# ProPrj_C64_Printer_Interface_2025-08-30.net
KiCad netlist of a schematic drawn in EasyEDA Pro
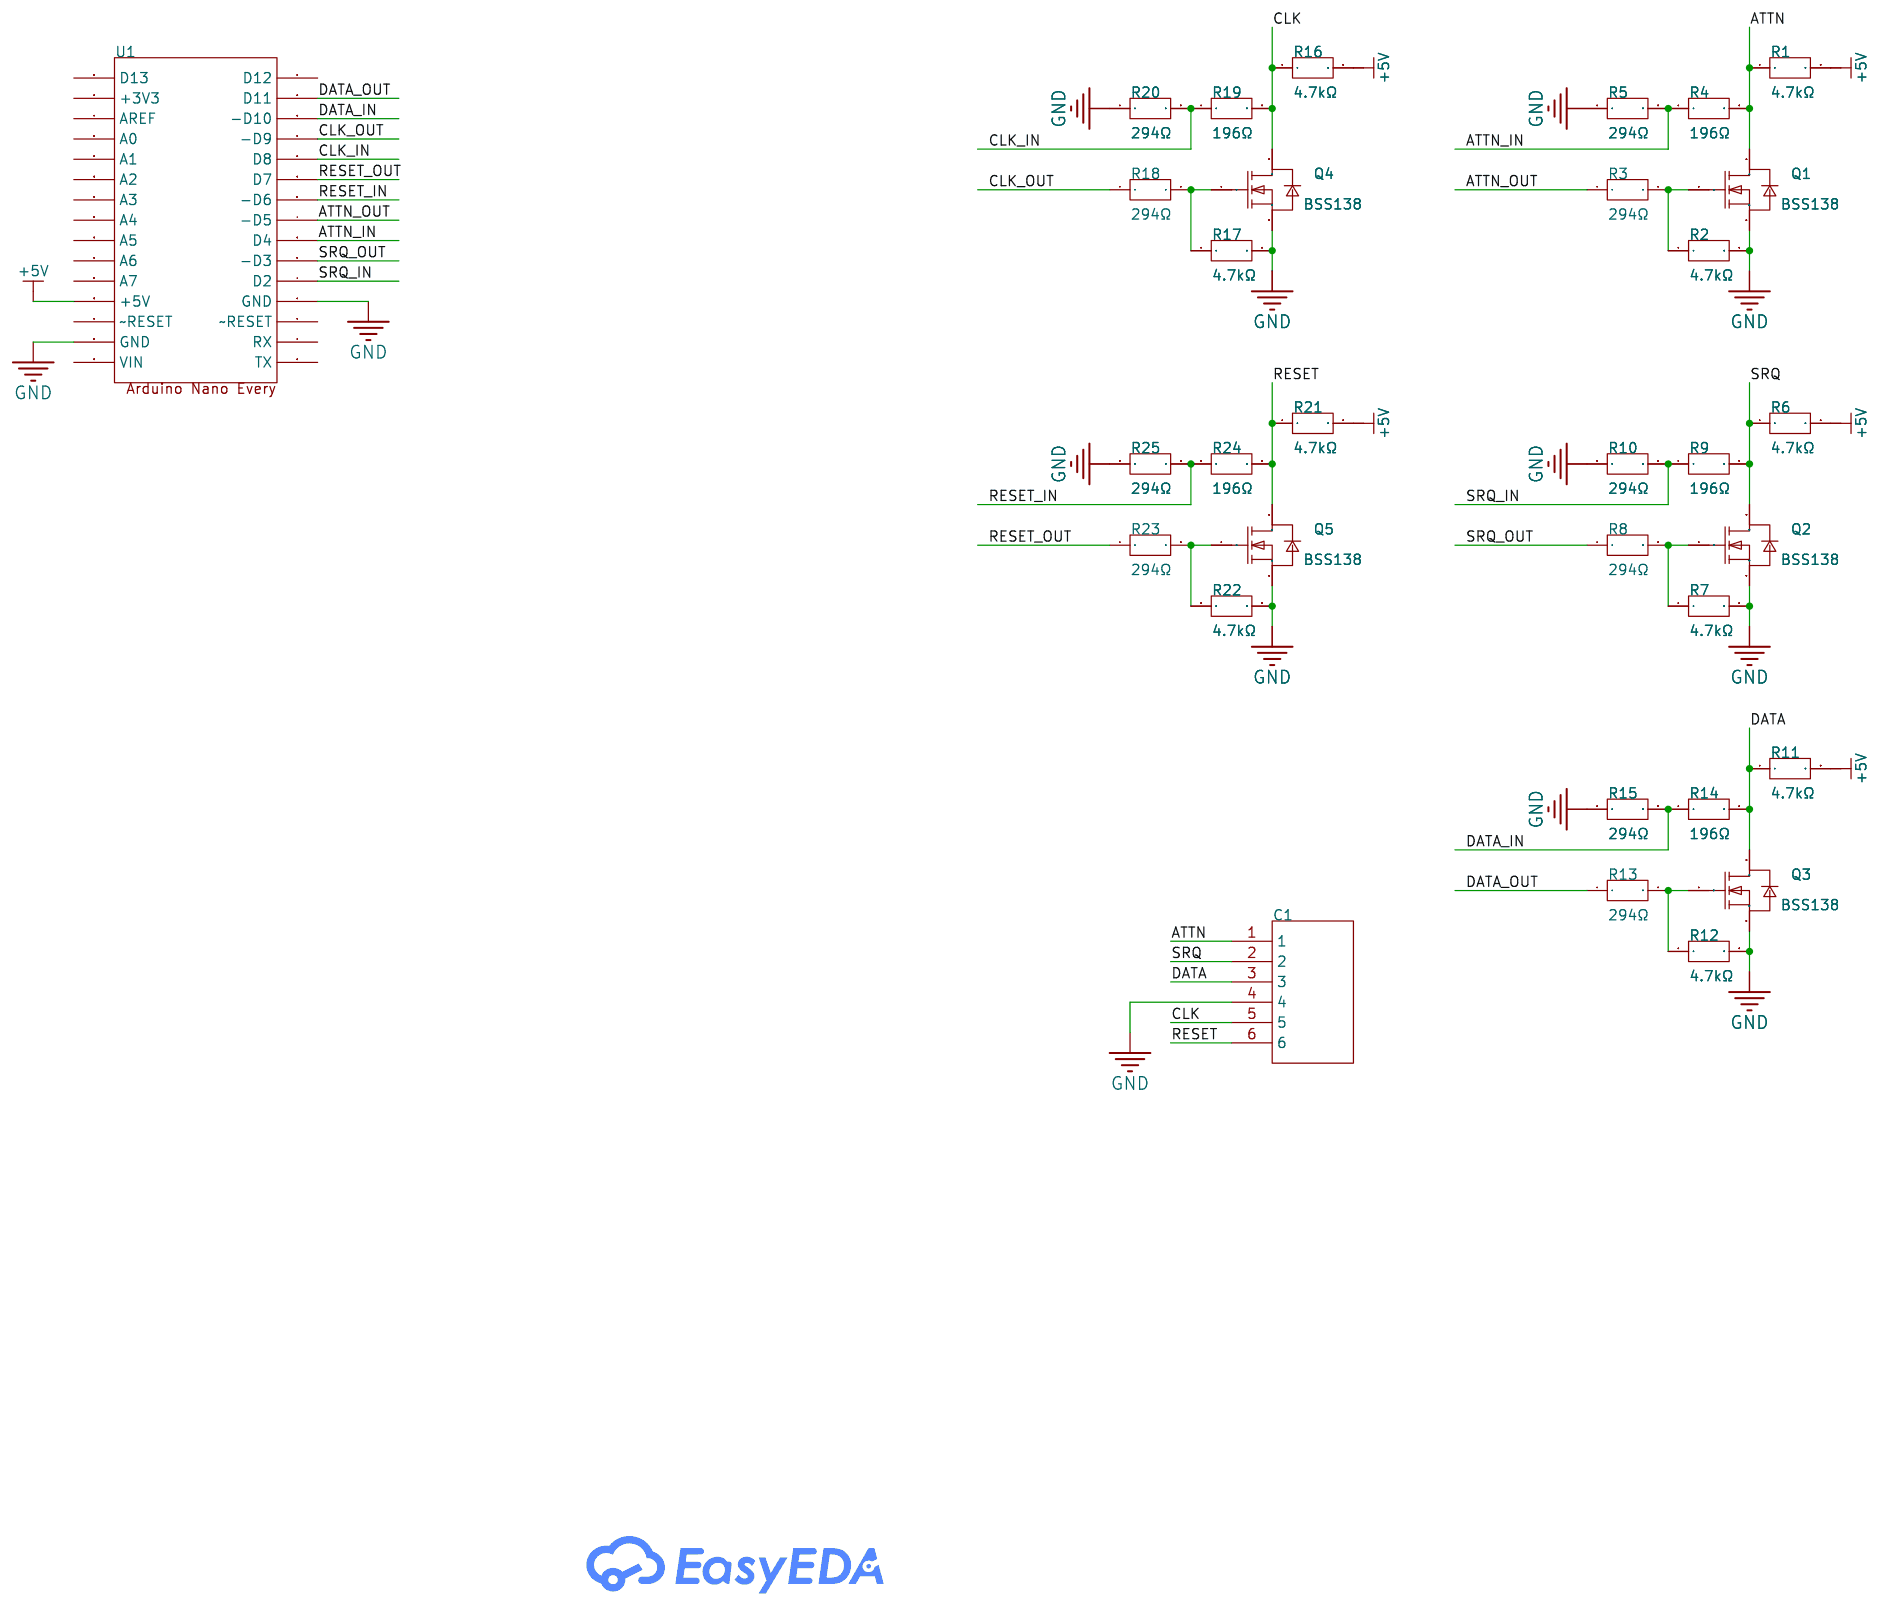
[diagram p0: schematic sheet]

(export (version "E")
  (design (tool "Eeschema 10.0.6"))
  (components
    (comp (ref "C1")
      (value "DIN 6")
      (footprint "easyedapro:FC680806")
      (libsource (lib "easyedapro") (part "FC680806 DIN 6 240°"))
    )
    (comp (ref "Q1")
      (value "BSS138")
      (footprint "easyedapro:SOT-23-3_L2.9-W1.3-P1.90-LS2.4-BR-1")
      (fields (field (name "Manufacturer") "KUU"))
      (libsource (lib "easyedapro") (part "BSS138_C3015220"))
    )
    (comp (ref "Q2")
      (value "BSS138")
      (footprint "easyedapro:SOT-23-3_L2.9-W1.3-P1.90-LS2.4-BR-1")
      (fields (field (name "Manufacturer") "KUU"))
      (libsource (lib "easyedapro") (part "BSS138_C3015220"))
    )
    (comp (ref "Q3")
      (value "BSS138")
      (footprint "easyedapro:SOT-23-3_L2.9-W1.3-P1.90-LS2.4-BR-1")
      (fields (field (name "Manufacturer") "KUU"))
      (libsource (lib "easyedapro") (part "BSS138_C3015220"))
    )
    (comp (ref "Q4")
      (value "BSS138")
      (footprint "easyedapro:SOT-23-3_L2.9-W1.3-P1.90-LS2.4-BR-1")
      (fields (field (name "Manufacturer") "KUU"))
      (libsource (lib "easyedapro") (part "BSS138_C3015220"))
    )
    (comp (ref "Q5")
      (value "BSS138")
      (footprint "easyedapro:SOT-23-3_L2.9-W1.3-P1.90-LS2.4-BR-1")
      (fields (field (name "Manufacturer") "KUU"))
      (libsource (lib "easyedapro") (part "BSS138_C3015220"))
    )
    (comp (ref "R1")
      (value "4.7kΩ")
      (footprint "easyedapro:R0805")
      (fields (field (name "Manufacturer Part") "RT0805BRD07330KL") (field (name "Manufacturer") "YAGEO(国巨)"))
      (libsource (lib "easyedapro") (part "RT0805BRD07330KL"))
    )
    (comp (ref "R2")
      (value "4.7kΩ")
      (footprint "easyedapro:R0805")
      (fields (field (name "Manufacturer Part") "RT0805BRD07330KL") (field (name "Manufacturer") "YAGEO(国巨)"))
      (libsource (lib "easyedapro") (part "RT0805BRD07330KL"))
    )
    (comp (ref "R3")
      (value "294Ω")
      (footprint "easyedapro:R0805")
      (fields (field (name "Manufacturer Part") "RT0805BRD07330KL") (field (name "Manufacturer") "YAGEO(国巨)"))
      (libsource (lib "easyedapro") (part "RT0805BRD07330KL"))
    )
    (comp (ref "R4")
      (value "196Ω")
      (footprint "easyedapro:R0805")
      (fields (field (name "Manufacturer Part") "RT0805BRD07330KL") (field (name "Manufacturer") "YAGEO(国巨)"))
      (libsource (lib "easyedapro") (part "RT0805BRD07330KL"))
    )
    (comp (ref "R5")
      (value "294Ω")
      (footprint "easyedapro:R0805")
      (fields (field (name "Manufacturer Part") "RT0805BRD07330KL") (field (name "Manufacturer") "YAGEO(国巨)"))
      (libsource (lib "easyedapro") (part "RT0805BRD07330KL"))
    )
    (comp (ref "R6")
      (value "4.7kΩ")
      (footprint "easyedapro:R0805")
      (fields (field (name "Manufacturer Part") "RT0805BRD07330KL") (field (name "Manufacturer") "YAGEO(国巨)"))
      (libsource (lib "easyedapro") (part "RT0805BRD07330KL"))
    )
    (comp (ref "R7")
      (value "4.7kΩ")
      (footprint "easyedapro:R0805")
      (fields (field (name "Manufacturer Part") "RT0805BRD07330KL") (field (name "Manufacturer") "YAGEO(国巨)"))
      (libsource (lib "easyedapro") (part "RT0805BRD07330KL"))
    )
    (comp (ref "R8")
      (value "294Ω")
      (footprint "easyedapro:R0805")
      (fields (field (name "Manufacturer Part") "RT0805BRD07330KL") (field (name "Manufacturer") "YAGEO(国巨)"))
      (libsource (lib "easyedapro") (part "RT0805BRD07330KL"))
    )
    (comp (ref "R9")
      (value "196Ω")
      (footprint "easyedapro:R0805")
      (fields (field (name "Manufacturer Part") "RT0805BRD07330KL") (field (name "Manufacturer") "YAGEO(国巨)"))
      (libsource (lib "easyedapro") (part "RT0805BRD07330KL"))
    )
    (comp (ref "R10")
      (value "294Ω")
      (footprint "easyedapro:R0805")
      (fields (field (name "Manufacturer Part") "RT0805BRD07330KL") (field (name "Manufacturer") "YAGEO(国巨)"))
      (libsource (lib "easyedapro") (part "RT0805BRD07330KL"))
    )
    (comp (ref "R11")
      (value "4.7kΩ")
      (footprint "easyedapro:R0805")
      (fields (field (name "Manufacturer Part") "RT0805BRD07330KL") (field (name "Manufacturer") "YAGEO(国巨)"))
      (libsource (lib "easyedapro") (part "RT0805BRD07330KL"))
    )
    (comp (ref "R12")
      (value "4.7kΩ")
      (footprint "easyedapro:R0805")
      (fields (field (name "Manufacturer Part") "RT0805BRD07330KL") (field (name "Manufacturer") "YAGEO(国巨)"))
      (libsource (lib "easyedapro") (part "RT0805BRD07330KL"))
    )
    (comp (ref "R13")
      (value "294Ω")
      (footprint "easyedapro:R0805")
      (fields (field (name "Manufacturer Part") "RT0805BRD07330KL") (field (name "Manufacturer") "YAGEO(国巨)"))
      (libsource (lib "easyedapro") (part "RT0805BRD07330KL"))
    )
    (comp (ref "R14")
      (value "196Ω")
      (footprint "easyedapro:R0805")
      (fields (field (name "Manufacturer Part") "RT0805BRD07330KL") (field (name "Manufacturer") "YAGEO(国巨)"))
      (libsource (lib "easyedapro") (part "RT0805BRD07330KL"))
    )
    (comp (ref "R15")
      (value "294Ω")
      (footprint "easyedapro:R0805")
      (fields (field (name "Manufacturer Part") "RT0805BRD07330KL") (field (name "Manufacturer") "YAGEO(国巨)"))
      (libsource (lib "easyedapro") (part "RT0805BRD07330KL"))
    )
    (comp (ref "R16")
      (value "4.7kΩ")
      (footprint "easyedapro:R0805")
      (fields (field (name "Manufacturer Part") "RT0805BRD07330KL") (field (name "Manufacturer") "YAGEO(国巨)"))
      (libsource (lib "easyedapro") (part "RT0805BRD07330KL"))
    )
    (comp (ref "R17")
      (value "4.7kΩ")
      (footprint "easyedapro:R0805")
      (fields (field (name "Manufacturer Part") "RT0805BRD07330KL") (field (name "Manufacturer") "YAGEO(国巨)"))
      (libsource (lib "easyedapro") (part "RT0805BRD07330KL"))
    )
    (comp (ref "R18")
      (value "294Ω")
      (footprint "easyedapro:R0805")
      (fields (field (name "Manufacturer Part") "RT0805BRD07330KL") (field (name "Manufacturer") "YAGEO(国巨)"))
      (libsource (lib "easyedapro") (part "RT0805BRD07330KL"))
    )
    (comp (ref "R19")
      (value "196Ω")
      (footprint "easyedapro:R0805")
      (fields (field (name "Manufacturer Part") "RT0805BRD07330KL") (field (name "Manufacturer") "YAGEO(国巨)"))
      (libsource (lib "easyedapro") (part "RT0805BRD07330KL"))
    )
    (comp (ref "R20")
      (value "294Ω")
      (footprint "easyedapro:R0805")
      (fields (field (name "Manufacturer Part") "RT0805BRD07330KL") (field (name "Manufacturer") "YAGEO(国巨)"))
      (libsource (lib "easyedapro") (part "RT0805BRD07330KL"))
    )
    (comp (ref "R21")
      (value "4.7kΩ")
      (footprint "easyedapro:R0805")
      (fields (field (name "Manufacturer Part") "RT0805BRD07330KL") (field (name "Manufacturer") "YAGEO(国巨)"))
      (libsource (lib "easyedapro") (part "RT0805BRD07330KL"))
    )
    (comp (ref "R22")
      (value "4.7kΩ")
      (footprint "easyedapro:R0805")
      (fields (field (name "Manufacturer Part") "RT0805BRD07330KL") (field (name "Manufacturer") "YAGEO(国巨)"))
      (libsource (lib "easyedapro") (part "RT0805BRD07330KL"))
    )
    (comp (ref "R23")
      (value "294Ω")
      (footprint "easyedapro:R0805")
      (fields (field (name "Manufacturer Part") "RT0805BRD07330KL") (field (name "Manufacturer") "YAGEO(国巨)"))
      (libsource (lib "easyedapro") (part "RT0805BRD07330KL"))
    )
    (comp (ref "R24")
      (value "196Ω")
      (footprint "easyedapro:R0805")
      (fields (field (name "Manufacturer Part") "RT0805BRD07330KL") (field (name "Manufacturer") "YAGEO(国巨)"))
      (libsource (lib "easyedapro") (part "RT0805BRD07330KL"))
    )
    (comp (ref "R25")
      (value "294Ω")
      (footprint "easyedapro:R0805")
      (fields (field (name "Manufacturer Part") "RT0805BRD07330KL") (field (name "Manufacturer") "YAGEO(国巨)"))
      (libsource (lib "easyedapro") (part "RT0805BRD07330KL"))
    )
    (comp (ref "U1")
      (value "~")
      (footprint "easyedapro:Arduino Nano Every (SMD)")
      (libsource (lib "easyedapro") (part "Arduino Nano Every"))
    )
  )
  (nets
    (net (code "1") (name "+5V") (class "Default")
      (node (ref "R1") (pin "2") (pinfunction "2_2") (pintype "unspecified"))
      (node (ref "R11") (pin "2") (pinfunction "2_2") (pintype "unspecified"))
      (node (ref "R16") (pin "2") (pinfunction "2_2") (pintype "unspecified"))
      (node (ref "R21") (pin "2") (pinfunction "2_2") (pintype "unspecified"))
      (node (ref "R6") (pin "2") (pinfunction "2_2") (pintype "unspecified"))
      (node (ref "U1") (pin "26") (pinfunction "+5V_26") (pintype "input"))
    )
    (net (code "2") (name "/ATTN") (class "Default")
      (node (ref "C1") (pin "1") (pinfunction "1_1") (pintype "input"))
      (node (ref "Q1") (pin "3") (pinfunction "D_3") (pintype "unspecified"))
      (node (ref "R1") (pin "1") (pinfunction "1_1") (pintype "unspecified"))
      (node (ref "R4") (pin "2") (pinfunction "2_2") (pintype "unspecified"))
    )
    (net (code "3") (name "/ATTN_IN") (class "Default")
      (node (ref "R4") (pin "1") (pinfunction "1_1") (pintype "unspecified"))
      (node (ref "R5") (pin "2") (pinfunction "2_2") (pintype "unspecified"))
      (node (ref "U1") (pin "6") (pinfunction "D4_6") (pintype "input"))
    )
    (net (code "4") (name "/ATTN_OUT") (class "Default")
      (node (ref "R3") (pin "1") (pinfunction "1_1") (pintype "unspecified"))
      (node (ref "U1") (pin "7") (pinfunction "-D5_7") (pintype "input"))
    )
    (net (code "5") (name "/CLK") (class "Default")
      (node (ref "C1") (pin "5") (pinfunction "5_5") (pintype "input"))
      (node (ref "Q4") (pin "3") (pinfunction "D_3") (pintype "unspecified"))
      (node (ref "R16") (pin "1") (pinfunction "1_1") (pintype "unspecified"))
      (node (ref "R19") (pin "2") (pinfunction "2_2") (pintype "unspecified"))
    )
    (net (code "6") (name "/CLK_IN") (class "Default")
      (node (ref "R19") (pin "1") (pinfunction "1_1") (pintype "unspecified"))
      (node (ref "R20") (pin "2") (pinfunction "2_2") (pintype "unspecified"))
      (node (ref "U1") (pin "10") (pinfunction "D8_10") (pintype "input"))
    )
    (net (code "7") (name "/CLK_OUT") (class "Default")
      (node (ref "R18") (pin "1") (pinfunction "1_1") (pintype "unspecified"))
      (node (ref "U1") (pin "11") (pinfunction "-D9_11") (pintype "input"))
    )
    (net (code "8") (name "/DATA") (class "Default")
      (node (ref "C1") (pin "3") (pinfunction "3_3") (pintype "input"))
      (node (ref "Q3") (pin "3") (pinfunction "D_3") (pintype "unspecified"))
      (node (ref "R11") (pin "1") (pinfunction "1_1") (pintype "unspecified"))
      (node (ref "R14") (pin "2") (pinfunction "2_2") (pintype "unspecified"))
    )
    (net (code "9") (name "/DATA_IN") (class "Default")
      (node (ref "R14") (pin "1") (pinfunction "1_1") (pintype "unspecified"))
      (node (ref "R15") (pin "2") (pinfunction "2_2") (pintype "unspecified"))
      (node (ref "U1") (pin "12") (pinfunction "-D10_12") (pintype "input"))
    )
    (net (code "10") (name "/DATA_OUT") (class "Default")
      (node (ref "R13") (pin "1") (pinfunction "1_1") (pintype "unspecified"))
      (node (ref "U1") (pin "13") (pinfunction "D11_13") (pintype "input"))
    )
    (net (code "11") (name "/RESET") (class "Default")
      (node (ref "C1") (pin "6") (pinfunction "6_6") (pintype "input"))
      (node (ref "Q5") (pin "3") (pinfunction "D_3") (pintype "unspecified"))
      (node (ref "R21") (pin "1") (pinfunction "1_1") (pintype "unspecified"))
      (node (ref "R24") (pin "2") (pinfunction "2_2") (pintype "unspecified"))
    )
    (net (code "12") (name "/RESET_IN") (class "Default")
      (node (ref "R24") (pin "1") (pinfunction "1_1") (pintype "unspecified"))
      (node (ref "R25") (pin "2") (pinfunction "2_2") (pintype "unspecified"))
      (node (ref "U1") (pin "8") (pinfunction "-D6_8") (pintype "input"))
    )
    (net (code "13") (name "/RESET_OUT") (class "Default")
      (node (ref "R23") (pin "1") (pinfunction "1_1") (pintype "unspecified"))
      (node (ref "U1") (pin "9") (pinfunction "D7_9") (pintype "input"))
    )
    (net (code "14") (name "/SRQ") (class "Default")
      (node (ref "C1") (pin "2") (pinfunction "2_2") (pintype "input"))
      (node (ref "Q2") (pin "3") (pinfunction "D_3") (pintype "unspecified"))
      (node (ref "R6") (pin "1") (pinfunction "1_1") (pintype "unspecified"))
      (node (ref "R9") (pin "2") (pinfunction "2_2") (pintype "unspecified"))
    )
    (net (code "15") (name "/SRQ_IN") (class "Default")
      (node (ref "R10") (pin "2") (pinfunction "2_2") (pintype "unspecified"))
      (node (ref "R9") (pin "1") (pinfunction "1_1") (pintype "unspecified"))
      (node (ref "U1") (pin "4") (pinfunction "D2_4") (pintype "input"))
    )
    (net (code "16") (name "/SRQ_OUT") (class "Default")
      (node (ref "R8") (pin "1") (pinfunction "1_1") (pintype "unspecified"))
      (node (ref "U1") (pin "5") (pinfunction "-D3_5") (pintype "input"))
    )
    (net (code "17") (name "GND") (class "Default")
      (node (ref "C1") (pin "4") (pinfunction "4_4") (pintype "input"))
      (node (ref "Q1") (pin "2") (pinfunction "S_2") (pintype "unspecified"))
      (node (ref "Q2") (pin "2") (pinfunction "S_2") (pintype "unspecified"))
      (node (ref "Q3") (pin "2") (pinfunction "S_2") (pintype "unspecified"))
      (node (ref "Q4") (pin "2") (pinfunction "S_2") (pintype "unspecified"))
      (node (ref "Q5") (pin "2") (pinfunction "S_2") (pintype "unspecified"))
      (node (ref "R10") (pin "1") (pinfunction "1_1") (pintype "unspecified"))
      (node (ref "R12") (pin "2") (pinfunction "2_2") (pintype "unspecified"))
      (node (ref "R15") (pin "1") (pinfunction "1_1") (pintype "unspecified"))
      (node (ref "R17") (pin "2") (pinfunction "2_2") (pintype "unspecified"))
      (node (ref "R2") (pin "2") (pinfunction "2_2") (pintype "unspecified"))
      (node (ref "R20") (pin "1") (pinfunction "1_1") (pintype "unspecified"))
      (node (ref "R22") (pin "2") (pinfunction "2_2") (pintype "unspecified"))
      (node (ref "R25") (pin "1") (pinfunction "1_1") (pintype "unspecified"))
      (node (ref "R5") (pin "1") (pinfunction "1_1") (pintype "unspecified"))
      (node (ref "R7") (pin "2") (pinfunction "2_2") (pintype "unspecified"))
      (node (ref "U1") (pin "28") (pinfunction "GND_28") (pintype "input"))
      (node (ref "U1") (pin "3") (pinfunction "GND_3") (pintype "input"))
    )
    (net (code "18") (name "Net-(Q1-G)") (class "Default")
      (node (ref "Q1") (pin "1") (pinfunction "G_1") (pintype "unspecified"))
      (node (ref "R2") (pin "1") (pinfunction "1_1") (pintype "unspecified"))
      (node (ref "R3") (pin "2") (pinfunction "2_2") (pintype "unspecified"))
    )
    (net (code "19") (name "Net-(Q2-G)") (class "Default")
      (node (ref "Q2") (pin "1") (pinfunction "G_1") (pintype "unspecified"))
      (node (ref "R7") (pin "1") (pinfunction "1_1") (pintype "unspecified"))
      (node (ref "R8") (pin "2") (pinfunction "2_2") (pintype "unspecified"))
    )
    (net (code "20") (name "Net-(Q3-G)") (class "Default")
      (node (ref "Q3") (pin "1") (pinfunction "G_1") (pintype "unspecified"))
      (node (ref "R12") (pin "1") (pinfunction "1_1") (pintype "unspecified"))
      (node (ref "R13") (pin "2") (pinfunction "2_2") (pintype "unspecified"))
    )
    (net (code "21") (name "Net-(Q4-G)") (class "Default")
      (node (ref "Q4") (pin "1") (pinfunction "G_1") (pintype "unspecified"))
      (node (ref "R17") (pin "1") (pinfunction "1_1") (pintype "unspecified"))
      (node (ref "R18") (pin "2") (pinfunction "2_2") (pintype "unspecified"))
    )
    (net (code "22") (name "Net-(Q5-G)") (class "Default")
      (node (ref "Q5") (pin "1") (pinfunction "G_1") (pintype "unspecified"))
      (node (ref "R22") (pin "1") (pinfunction "1_1") (pintype "unspecified"))
      (node (ref "R23") (pin "2") (pinfunction "2_2") (pintype "unspecified"))
    )
    (net (code "23") (name "unconnected-(U1-+3V3-Pad16)") (class "Default")
      (node (ref "U1") (pin "16") (pinfunction "+3V3_16") (pintype "input"))
    )
    (net (code "24") (name "unconnected-(U1-A0-Pad18)") (class "Default")
      (node (ref "U1") (pin "18") (pinfunction "A0_18") (pintype "input"))
    )
    (net (code "25") (name "unconnected-(U1-A1-Pad19)") (class "Default")
      (node (ref "U1") (pin "19") (pinfunction "A1_19") (pintype "input"))
    )
    (net (code "26") (name "unconnected-(U1-A2-Pad20)") (class "Default")
      (node (ref "U1") (pin "20") (pinfunction "A2_20") (pintype "input"))
    )
    (net (code "27") (name "unconnected-(U1-A3-Pad21)") (class "Default")
      (node (ref "U1") (pin "21") (pinfunction "A3_21") (pintype "input"))
    )
    (net (code "28") (name "unconnected-(U1-A4-Pad22)") (class "Default")
      (node (ref "U1") (pin "22") (pinfunction "A4_22") (pintype "input"))
    )
    (net (code "29") (name "unconnected-(U1-A5-Pad23)") (class "Default")
      (node (ref "U1") (pin "23") (pinfunction "A5_23") (pintype "input"))
    )
    (net (code "30") (name "unconnected-(U1-A6-Pad24)") (class "Default")
      (node (ref "U1") (pin "24") (pinfunction "A6_24") (pintype "input"))
    )
    (net (code "31") (name "unconnected-(U1-A7-Pad25)") (class "Default")
      (node (ref "U1") (pin "25") (pinfunction "A7_25") (pintype "input"))
    )
    (net (code "32") (name "unconnected-(U1-AREF-Pad17)") (class "Default")
      (node (ref "U1") (pin "17") (pinfunction "AREF_17") (pintype "input"))
    )
    (net (code "33") (name "unconnected-(U1-D12-Pad14)") (class "Default")
      (node (ref "U1") (pin "14") (pinfunction "D12_14") (pintype "input"))
    )
    (net (code "34") (name "unconnected-(U1-D13-Pad15)") (class "Default")
      (node (ref "U1") (pin "15") (pinfunction "D13_15") (pintype "input"))
    )
    (net (code "35") (name "unconnected-(U1-RX-Pad1)") (class "Default")
      (node (ref "U1") (pin "1") (pinfunction "RX_1") (pintype "input"))
    )
    (net (code "36") (name "unconnected-(U1-TX-Pad0)") (class "Default")
      (node (ref "U1") (pin "0") (pinfunction "TX_0") (pintype "input"))
    )
    (net (code "37") (name "unconnected-(U1-VIN-Pad29)") (class "Default")
      (node (ref "U1") (pin "29") (pinfunction "VIN_29") (pintype "input"))
    )
    (net (code "38") (name "unconnected-(U1-~RESET-Pad2)") (class "Default")
      (node (ref "U1") (pin "2") (pinfunction "~RESET_2") (pintype "input"))
    )
    (net (code "39") (name "unconnected-(U1-~RESET-Pad27)") (class "Default")
      (node (ref "U1") (pin "27") (pinfunction "~RESET_27") (pintype "input"))
    )
  )
)
